# ST-Link.net
KiCad netlist of a schematic drawn in Altium Designer
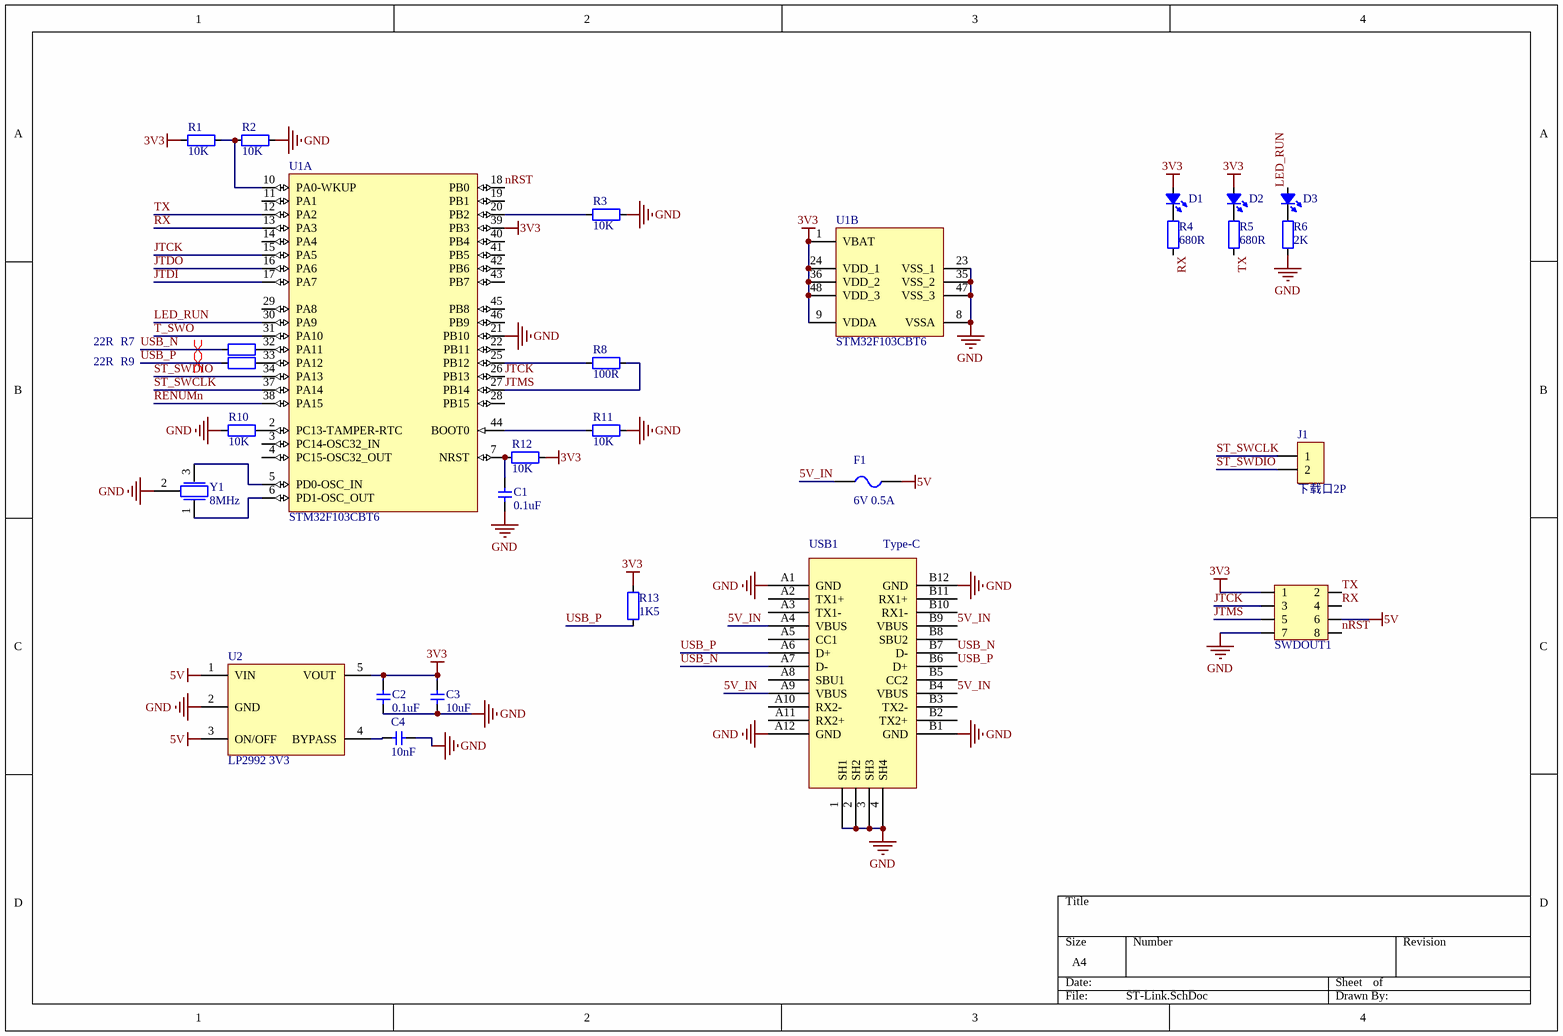
[diagram p0: ST-Link.SchDoc]

(export (version "E")
  (design (tool "Eeschema 10.0.6"))
  (components
    (comp (ref "C1")
      (value "0.1uF")
      (footprint "1.00-YltsPcbLib:0603_CAP")
      (description "电容")
      (libsource (lib "0.0 - YltsSchlib") (part "电容-0603"))
    )
    (comp (ref "C2")
      (value "0.1uF")
      (footprint "1.00-YltsPcbLib:0603_CAP")
      (description "电容")
      (libsource (lib "0.0 - YltsSchlib") (part "电容-0603"))
    )
    (comp (ref "C3")
      (value "10uF")
      (footprint "1.00-YltsPcbLib:0603_CAP")
      (description "电容")
      (libsource (lib "0.0 - YltsSchlib") (part "电容-0603"))
    )
    (comp (ref "C4")
      (value "10nF")
      (footprint "1.00-YltsPcbLib:0603_CAP")
      (description "电容")
      (libsource (lib "0.0 - YltsSchlib") (part "电容-0603"))
    )
    (comp (ref "D1")
      (value "LED-0603")
      (footprint "1.00-YltsPcbLib:0603_LED_RED")
      (description "发光二极管")
      (libsource (lib "0.0 - YltsSchlib") (part "二极管-0603-RED"))
    )
    (comp (ref "D2")
      (value "LED-0603")
      (footprint "1.00-YltsPcbLib:0603_LED_RED")
      (description "发光二极管")
      (libsource (lib "0.0 - YltsSchlib") (part "二极管-0603-RED"))
    )
    (comp (ref "D3")
      (value "LED-0603")
      (footprint "1.00-YltsPcbLib:0603_LED_RED")
      (description "发光二极管")
      (libsource (lib "0.0 - YltsSchlib") (part "二极管-0603-RED"))
    )
    (comp (ref "F1")
      (value "6V 0.5A")
      (footprint "FU 0805")
      (description "贴片保险丝")
      (fields (field (name "版权归属") "封装库来自淘宝卖家 ID：黄晶宝石"))
      (libsource (lib "2.0 - 保险丝-晶振-光耦") (part "FU"))
    )
    (comp (ref "J1")
      (value "下载口2P")
      (footprint "下载口2P-1.27")
      (description "下载口2P SWD")
      (libsource (lib "0.0 - YltsSchlib") (part "接插件-下载口2P"))
    )
    (comp (ref "R1")
      (value "10K")
      (footprint "1.00-YltsPcbLib:0603_RES")
      (description "电阻")
      (libsource (lib "0.0 - YltsSchlib") (part "电阻-0603"))
    )
    (comp (ref "R2")
      (value "10K")
      (footprint "1.00-YltsPcbLib:0603_RES")
      (description "电阻")
      (libsource (lib "0.0 - YltsSchlib") (part "电阻-0603"))
    )
    (comp (ref "R3")
      (value "10K")
      (footprint "1.00-YltsPcbLib:0603_RES")
      (description "电阻")
      (libsource (lib "0.0 - YltsSchlib") (part "电阻-0603"))
    )
    (comp (ref "R4")
      (value "680R")
      (footprint "1.00-YltsPcbLib:0603_RES")
      (description "电阻")
      (libsource (lib "") (part "电阻-0603_1"))
    )
    (comp (ref "R5")
      (value "680R")
      (footprint "1.00-YltsPcbLib:0603_RES")
      (description "电阻")
      (libsource (lib "") (part "电阻-0603_1"))
    )
    (comp (ref "R6")
      (value "2K")
      (footprint "1.00-YltsPcbLib:0603_RES")
      (description "电阻")
      (libsource (lib "") (part "电阻-0603_1"))
    )
    (comp (ref "R7")
      (value "22R")
      (footprint "1.00-YltsPcbLib:0603_RES")
      (description "电阻")
      (libsource (lib "0.0 - YltsSchlib") (part "电阻-0603"))
    )
    (comp (ref "R8")
      (value "100R")
      (footprint "1.00-YltsPcbLib:0603_RES")
      (description "电阻")
      (libsource (lib "0.0 - YltsSchlib") (part "电阻-0603"))
    )
    (comp (ref "R9")
      (value "22R")
      (footprint "1.00-YltsPcbLib:0603_RES")
      (description "电阻")
      (libsource (lib "0.0 - YltsSchlib") (part "电阻-0603"))
    )
    (comp (ref "R10")
      (value "10K")
      (footprint "1.00-YltsPcbLib:0603_RES")
      (description "电阻")
      (libsource (lib "0.0 - YltsSchlib") (part "电阻-0603"))
    )
    (comp (ref "R11")
      (value "10K")
      (footprint "1.00-YltsPcbLib:0603_RES")
      (description "电阻")
      (libsource (lib "0.0 - YltsSchlib") (part "电阻-0603"))
    )
    (comp (ref "R12")
      (value "10K")
      (footprint "1.00-YltsPcbLib:0603_RES")
      (description "电阻")
      (libsource (lib "0.0 - YltsSchlib") (part "电阻-0603"))
    )
    (comp (ref "R13")
      (value "1K5")
      (footprint "1.00-YltsPcbLib:0603_RES")
      (description "电阻")
      (libsource (lib "") (part "电阻-0603_1"))
    )
    (comp (ref "SWDOUT1")
      (value "HDR2x4_2.54")
      (footprint "HDR2X4_2.54_180H")
      (description "Header")
      (libsource (lib "MyPcbLib") (part "HDR2x4_2.54"))
    )
    (comp (ref "U1")
      (value "STM32F103CBT6")
      (footprint "LQFP-48")
      (libsource (lib "STMicroelectronics STM32 F1") (part "STM32F103CBT6"))
    )
    (comp (ref "U2")
      (value "LP2992 3V3")
      (footprint "SOT23-5")
      (description "LDO")
      (libsource (lib "MyPcbLib") (part "LP2992"))
    )
    (comp (ref "USB1")
      (value "Type-C")
      (footprint "Type-C-TOP")
      (libsource (lib "MyPcbLib") (part "USB-Type-C-TOP"))
    )
    (comp (ref "Y1")
      (value "8MHz")
      (footprint "晶振-3P")
      (description "村田贴片")
      (libsource (lib "MyPcbLib") (part "晶振-3Pin"))
    )
  )
  (nets
    (net (code "1") (name "/5V_IN") (class "Default")
      (node (ref "F1") (pin "1") (pinfunction "1_1") (pintype "passive"))
      (node (ref "USB1") (pin "A4") (pinfunction "VBUS_A4") (pintype "passive"))
      (node (ref "USB1") (pin "A9") (pinfunction "VBUS_A9") (pintype "passive"))
      (node (ref "USB1") (pin "B4") (pinfunction "VBUS_B4") (pintype "passive"))
      (node (ref "USB1") (pin "B9") (pinfunction "VBUS_B9") (pintype "passive"))
    )
    (net (code "2") (name "/JTCK") (class "Default")
      (node (ref "SWDOUT1") (pin "3") (pinfunction "3_3") (pintype "passive"))
      (node (ref "U1") (pin "15") (pinfunction "PA5_15") (pintype "bidirectional"))
      (node (ref "U1") (pin "26") (pinfunction "PB13_26") (pintype "bidirectional"))
    )
    (net (code "3") (name "/JTDI") (class "Default")
      (node (ref "U1") (pin "17") (pinfunction "PA7_17") (pintype "bidirectional"))
    )
    (net (code "4") (name "/JTDO") (class "Default")
      (node (ref "U1") (pin "16") (pinfunction "PA6_16") (pintype "bidirectional"))
    )
    (net (code "5") (name "/JTMS") (class "Default")
      (node (ref "R8") (pin "2") (pinfunction "2_2") (pintype "passive"))
      (node (ref "SWDOUT1") (pin "5") (pinfunction "5_5") (pintype "passive"))
      (node (ref "U1") (pin "27") (pinfunction "PB14_27") (pintype "bidirectional"))
    )
    (net (code "6") (name "/LED_RUN") (class "Default")
      (node (ref "D3") (pin "1") (pinfunction "A_1") (pintype "passive"))
      (node (ref "U1") (pin "30") (pinfunction "PA9_30") (pintype "bidirectional"))
    )
    (net (code "7") (name "/RENUMn") (class "Default")
      (node (ref "U1") (pin "38") (pinfunction "PA15_38") (pintype "bidirectional"))
    )
    (net (code "8") (name "/RX") (class "Default")
      (node (ref "R4") (pin "1") (pinfunction "1_1") (pintype "passive"))
      (node (ref "SWDOUT1") (pin "4") (pinfunction "4_4") (pintype "passive"))
      (node (ref "U1") (pin "13") (pinfunction "PA3_13") (pintype "bidirectional"))
    )
    (net (code "9") (name "/ST_SWCLK") (class "Default")
      (node (ref "J1") (pin "1") (pinfunction "1_1") (pintype "passive"))
      (node (ref "U1") (pin "37") (pinfunction "PA14_37") (pintype "bidirectional"))
    )
    (net (code "10") (name "/ST_SWDIO") (class "Default")
      (node (ref "J1") (pin "2") (pinfunction "2_2") (pintype "passive"))
      (node (ref "U1") (pin "34") (pinfunction "PA13_34") (pintype "bidirectional"))
    )
    (net (code "11") (name "/TX") (class "Default")
      (node (ref "R5") (pin "1") (pinfunction "1_1") (pintype "passive"))
      (node (ref "SWDOUT1") (pin "2") (pinfunction "2_2") (pintype "passive"))
      (node (ref "U1") (pin "12") (pinfunction "PA2_12") (pintype "bidirectional"))
    )
    (net (code "12") (name "/T_SWO") (class "Default")
      (node (ref "U1") (pin "31") (pinfunction "PA10_31") (pintype "bidirectional"))
    )
    (net (code "13") (name "/USB_N") (class "Default")
      (node (ref "R7") (pin "1") (pinfunction "1_1") (pintype "passive"))
      (node (ref "USB1") (pin "A7") (pinfunction "D-_A7") (pintype "passive"))
      (node (ref "USB1") (pin "B7") (pinfunction "D-_B7") (pintype "passive"))
    )
    (net (code "14") (name "/USB_P") (class "Default")
      (node (ref "R13") (pin "1") (pinfunction "1_1") (pintype "passive"))
      (node (ref "R9") (pin "1") (pinfunction "1_1") (pintype "passive"))
      (node (ref "USB1") (pin "A6") (pinfunction "D+_A6") (pintype "passive"))
      (node (ref "USB1") (pin "B6") (pinfunction "D+_B6") (pintype "passive"))
    )
    (net (code "15") (name "/nRST") (class "Default")
      (node (ref "SWDOUT1") (pin "8") (pinfunction "8_8") (pintype "passive"))
      (node (ref "U1") (pin "18") (pinfunction "PB0_18") (pintype "bidirectional"))
    )
    (net (code "16") (name "3V3") (class "Default")
      (node (ref "C2") (pin "2") (pinfunction "2_2") (pintype "passive"))
      (node (ref "C3") (pin "2") (pinfunction "2_2") (pintype "passive"))
      (node (ref "D1") (pin "1") (pinfunction "A_1") (pintype "passive"))
      (node (ref "D2") (pin "1") (pinfunction "A_1") (pintype "passive"))
      (node (ref "R1") (pin "1") (pinfunction "1_1") (pintype "passive"))
      (node (ref "R12") (pin "2") (pinfunction "2_2") (pintype "passive"))
      (node (ref "R13") (pin "2") (pinfunction "2_2") (pintype "passive"))
      (node (ref "SWDOUT1") (pin "1") (pinfunction "1_1") (pintype "passive"))
      (node (ref "U1") (pin "1") (pinfunction "VBAT_1") (pintype "power_in"))
      (node (ref "U1") (pin "24") (pinfunction "VDD_1_24") (pintype "power_in"))
      (node (ref "U1") (pin "36") (pinfunction "VDD_2_36") (pintype "power_in"))
      (node (ref "U1") (pin "39") (pinfunction "PB3_39") (pintype "bidirectional"))
      (node (ref "U1") (pin "48") (pinfunction "VDD_3_48") (pintype "power_in"))
      (node (ref "U1") (pin "9") (pinfunction "VDDA_9") (pintype "power_in"))
      (node (ref "U2") (pin "5") (pinfunction "VOUT_5") (pintype "passive"))
    )
    (net (code "17") (name "5V") (class "Default")
      (node (ref "F1") (pin "2") (pinfunction "2_2") (pintype "passive"))
      (node (ref "SWDOUT1") (pin "6") (pinfunction "6_6") (pintype "passive"))
      (node (ref "U2") (pin "1") (pinfunction "VIN_1") (pintype "passive"))
      (node (ref "U2") (pin "3") (pinfunction "ON/OFF_3") (pintype "passive"))
    )
    (net (code "18") (name "GND") (class "Default")
      (node (ref "C1") (pin "1") (pinfunction "1_1") (pintype "passive"))
      (node (ref "C2") (pin "1") (pinfunction "1_1") (pintype "passive"))
      (node (ref "C3") (pin "1") (pinfunction "1_1") (pintype "passive"))
      (node (ref "C4") (pin "1") (pinfunction "1_1") (pintype "passive"))
      (node (ref "R10") (pin "1") (pinfunction "1_1") (pintype "passive"))
      (node (ref "R11") (pin "2") (pinfunction "2_2") (pintype "passive"))
      (node (ref "R2") (pin "2") (pinfunction "2_2") (pintype "passive"))
      (node (ref "R3") (pin "2") (pinfunction "2_2") (pintype "passive"))
      (node (ref "R6") (pin "1") (pinfunction "1_1") (pintype "passive"))
      (node (ref "SWDOUT1") (pin "7") (pinfunction "7_7") (pintype "passive"))
      (node (ref "U1") (pin "21") (pinfunction "PB10_21") (pintype "bidirectional"))
      (node (ref "U1") (pin "23") (pinfunction "VSS_1_23") (pintype "power_in"))
      (node (ref "U1") (pin "35") (pinfunction "VSS_2_35") (pintype "power_in"))
      (node (ref "U1") (pin "47") (pinfunction "VSS_3_47") (pintype "power_in"))
      (node (ref "U1") (pin "8") (pinfunction "VSSA_8") (pintype "power_in"))
      (node (ref "U2") (pin "2") (pinfunction "GND_2") (pintype "passive"))
      (node (ref "USB1") (pin "1") (pinfunction "SH1_1") (pintype "passive"))
      (node (ref "USB1") (pin "2") (pinfunction "SH2_2") (pintype "passive"))
      (node (ref "USB1") (pin "3") (pinfunction "SH3_3") (pintype "passive"))
      (node (ref "USB1") (pin "4") (pinfunction "SH4_4") (pintype "passive"))
      (node (ref "USB1") (pin "A1") (pinfunction "GND_A1") (pintype "passive"))
      (node (ref "USB1") (pin "A12") (pinfunction "GND_A12") (pintype "passive"))
      (node (ref "USB1") (pin "B1") (pinfunction "GND_B1") (pintype "passive"))
      (node (ref "USB1") (pin "B12") (pinfunction "GND_B12") (pintype "passive"))
      (node (ref "Y1") (pin "2") (pinfunction "2_2") (pintype "passive"))
    )
    (net (code "19") (name "Net-(D1-K)") (class "Default")
      (node (ref "D1") (pin "2") (pinfunction "K_2") (pintype "passive"))
      (node (ref "R4") (pin "2") (pinfunction "2_2") (pintype "passive"))
    )
    (net (code "20") (name "Net-(D2-K)") (class "Default")
      (node (ref "D2") (pin "2") (pinfunction "K_2") (pintype "passive"))
      (node (ref "R5") (pin "2") (pinfunction "2_2") (pintype "passive"))
    )
    (net (code "21") (name "Net-(D3-K)") (class "Default")
      (node (ref "D3") (pin "2") (pinfunction "K_2") (pintype "passive"))
      (node (ref "R6") (pin "2") (pinfunction "2_2") (pintype "passive"))
    )
    (net (code "22") (name "Net-(U1A-BOOT0)") (class "Default")
      (node (ref "R11") (pin "1") (pinfunction "1_1") (pintype "passive"))
      (node (ref "U1") (pin "44") (pinfunction "BOOT0_44") (pintype "input"))
    )
    (net (code "23") (name "Net-(U1A-NRST)") (class "Default")
      (node (ref "C1") (pin "2") (pinfunction "2_2") (pintype "passive"))
      (node (ref "R12") (pin "1") (pinfunction "1_1") (pintype "passive"))
      (node (ref "U1") (pin "7") (pinfunction "NRST_7") (pintype "bidirectional"))
    )
    (net (code "24") (name "Net-(U1A-PA0-WKUP)") (class "Default")
      (node (ref "R1") (pin "2") (pinfunction "2_2") (pintype "passive"))
      (node (ref "R2") (pin "1") (pinfunction "1_1") (pintype "passive"))
      (node (ref "U1") (pin "10") (pinfunction "PA0-WKUP_10") (pintype "bidirectional"))
    )
    (net (code "25") (name "Net-(U1A-PA11)") (class "Default")
      (node (ref "R7") (pin "2") (pinfunction "2_2") (pintype "passive"))
      (node (ref "U1") (pin "32") (pinfunction "PA11_32") (pintype "bidirectional"))
    )
    (net (code "26") (name "Net-(U1A-PA12)") (class "Default")
      (node (ref "R9") (pin "2") (pinfunction "2_2") (pintype "passive"))
      (node (ref "U1") (pin "33") (pinfunction "PA12_33") (pintype "bidirectional"))
    )
    (net (code "27") (name "Net-(U1A-PB2)") (class "Default")
      (node (ref "R3") (pin "1") (pinfunction "1_1") (pintype "passive"))
      (node (ref "U1") (pin "20") (pinfunction "PB2_20") (pintype "bidirectional"))
    )
    (net (code "28") (name "Net-(U1A-PB12)") (class "Default")
      (node (ref "R8") (pin "1") (pinfunction "1_1") (pintype "passive"))
      (node (ref "U1") (pin "25") (pinfunction "PB12_25") (pintype "bidirectional"))
    )
    (net (code "29") (name "Net-(U1A-PC13-TAMPER-RTC)") (class "Default")
      (node (ref "R10") (pin "2") (pinfunction "2_2") (pintype "passive"))
      (node (ref "U1") (pin "2") (pinfunction "PC13-TAMPER-RTC_2") (pintype "bidirectional"))
    )
    (net (code "30") (name "Net-(U1A-PD0-OSC_IN)") (class "Default")
      (node (ref "U1") (pin "5") (pinfunction "PD0-OSC_IN_5") (pintype "bidirectional"))
      (node (ref "Y1") (pin "3") (pinfunction "3_3") (pintype "passive"))
    )
    (net (code "31") (name "Net-(U1A-PD1-OSC_OUT)") (class "Default")
      (node (ref "U1") (pin "6") (pinfunction "PD1-OSC_OUT_6") (pintype "bidirectional"))
      (node (ref "Y1") (pin "1") (pinfunction "1_1") (pintype "passive"))
    )
    (net (code "32") (name "Net-(U2-BYPASS)") (class "Default")
      (node (ref "C4") (pin "2") (pinfunction "2_2") (pintype "passive"))
      (node (ref "U2") (pin "4") (pinfunction "BYPASS_4") (pintype "passive"))
    )
    (net (code "33") (name "unconnected-(U1A-PA1-Pad11)") (class "Default")
      (node (ref "U1") (pin "11") (pinfunction "PA1_11") (pintype "bidirectional"))
    )
    (net (code "34") (name "unconnected-(U1A-PA4-Pad14)") (class "Default")
      (node (ref "U1") (pin "14") (pinfunction "PA4_14") (pintype "bidirectional"))
    )
    (net (code "35") (name "unconnected-(U1A-PA8-Pad29)") (class "Default")
      (node (ref "U1") (pin "29") (pinfunction "PA8_29") (pintype "bidirectional"))
    )
    (net (code "36") (name "unconnected-(U1A-PB1-Pad19)") (class "Default")
      (node (ref "U1") (pin "19") (pinfunction "PB1_19") (pintype "bidirectional"))
    )
    (net (code "37") (name "unconnected-(U1A-PB4-Pad40)") (class "Default")
      (node (ref "U1") (pin "40") (pinfunction "PB4_40") (pintype "bidirectional"))
    )
    (net (code "38") (name "unconnected-(U1A-PB5-Pad41)") (class "Default")
      (node (ref "U1") (pin "41") (pinfunction "PB5_41") (pintype "bidirectional"))
    )
    (net (code "39") (name "unconnected-(U1A-PB6-Pad42)") (class "Default")
      (node (ref "U1") (pin "42") (pinfunction "PB6_42") (pintype "bidirectional"))
    )
    (net (code "40") (name "unconnected-(U1A-PB7-Pad43)") (class "Default")
      (node (ref "U1") (pin "43") (pinfunction "PB7_43") (pintype "bidirectional"))
    )
    (net (code "41") (name "unconnected-(U1A-PB8-Pad45)") (class "Default")
      (node (ref "U1") (pin "45") (pinfunction "PB8_45") (pintype "bidirectional"))
    )
    (net (code "42") (name "unconnected-(U1A-PB9-Pad46)") (class "Default")
      (node (ref "U1") (pin "46") (pinfunction "PB9_46") (pintype "bidirectional"))
    )
    (net (code "43") (name "unconnected-(U1A-PB11-Pad22)") (class "Default")
      (node (ref "U1") (pin "22") (pinfunction "PB11_22") (pintype "bidirectional"))
    )
    (net (code "44") (name "unconnected-(U1A-PB15-Pad28)") (class "Default")
      (node (ref "U1") (pin "28") (pinfunction "PB15_28") (pintype "bidirectional"))
    )
    (net (code "45") (name "unconnected-(U1A-PC14-OSC32_IN-Pad3)") (class "Default")
      (node (ref "U1") (pin "3") (pinfunction "PC14-OSC32_IN_3") (pintype "bidirectional"))
    )
    (net (code "46") (name "unconnected-(U1A-PC15-OSC32_OUT-Pad4)") (class "Default")
      (node (ref "U1") (pin "4") (pinfunction "PC15-OSC32_OUT_4") (pintype "bidirectional"))
    )
    (net (code "47") (name "unconnected-(USB1-CC1-PadA5)") (class "Default")
      (node (ref "USB1") (pin "A5") (pinfunction "CC1_A5") (pintype "passive"))
    )
    (net (code "48") (name "unconnected-(USB1-CC2-PadB5)") (class "Default")
      (node (ref "USB1") (pin "B5") (pinfunction "CC2_B5") (pintype "passive"))
    )
    (net (code "49") (name "unconnected-(USB1-RX1+-PadB11)") (class "Default")
      (node (ref "USB1") (pin "B11") (pinfunction "RX1+_B11") (pintype "passive"))
    )
    (net (code "50") (name "unconnected-(USB1-RX1--PadB10)") (class "Default")
      (node (ref "USB1") (pin "B10") (pinfunction "RX1-_B10") (pintype "passive"))
    )
    (net (code "51") (name "unconnected-(USB1-RX2+-PadA11)") (class "Default")
      (node (ref "USB1") (pin "A11") (pinfunction "RX2+_A11") (pintype "passive"))
    )
    (net (code "52") (name "unconnected-(USB1-RX2--PadA10)") (class "Default")
      (node (ref "USB1") (pin "A10") (pinfunction "RX2-_A10") (pintype "passive"))
    )
    (net (code "53") (name "unconnected-(USB1-SBU1-PadA8)") (class "Default")
      (node (ref "USB1") (pin "A8") (pinfunction "SBU1_A8") (pintype "passive"))
    )
    (net (code "54") (name "unconnected-(USB1-SBU2-PadB8)") (class "Default")
      (node (ref "USB1") (pin "B8") (pinfunction "SBU2_B8") (pintype "passive"))
    )
    (net (code "55") (name "unconnected-(USB1-TX1+-PadA2)") (class "Default")
      (node (ref "USB1") (pin "A2") (pinfunction "TX1+_A2") (pintype "passive"))
    )
    (net (code "56") (name "unconnected-(USB1-TX1--PadA3)") (class "Default")
      (node (ref "USB1") (pin "A3") (pinfunction "TX1-_A3") (pintype "passive"))
    )
    (net (code "57") (name "unconnected-(USB1-TX2+-PadB2)") (class "Default")
      (node (ref "USB1") (pin "B2") (pinfunction "TX2+_B2") (pintype "passive"))
    )
    (net (code "58") (name "unconnected-(USB1-TX2--PadB3)") (class "Default")
      (node (ref "USB1") (pin "B3") (pinfunction "TX2-_B3") (pintype "passive"))
    )
  )
)
